# LED_ROWS.net
KiCad netlist of a schematic drawn in Altium Designer
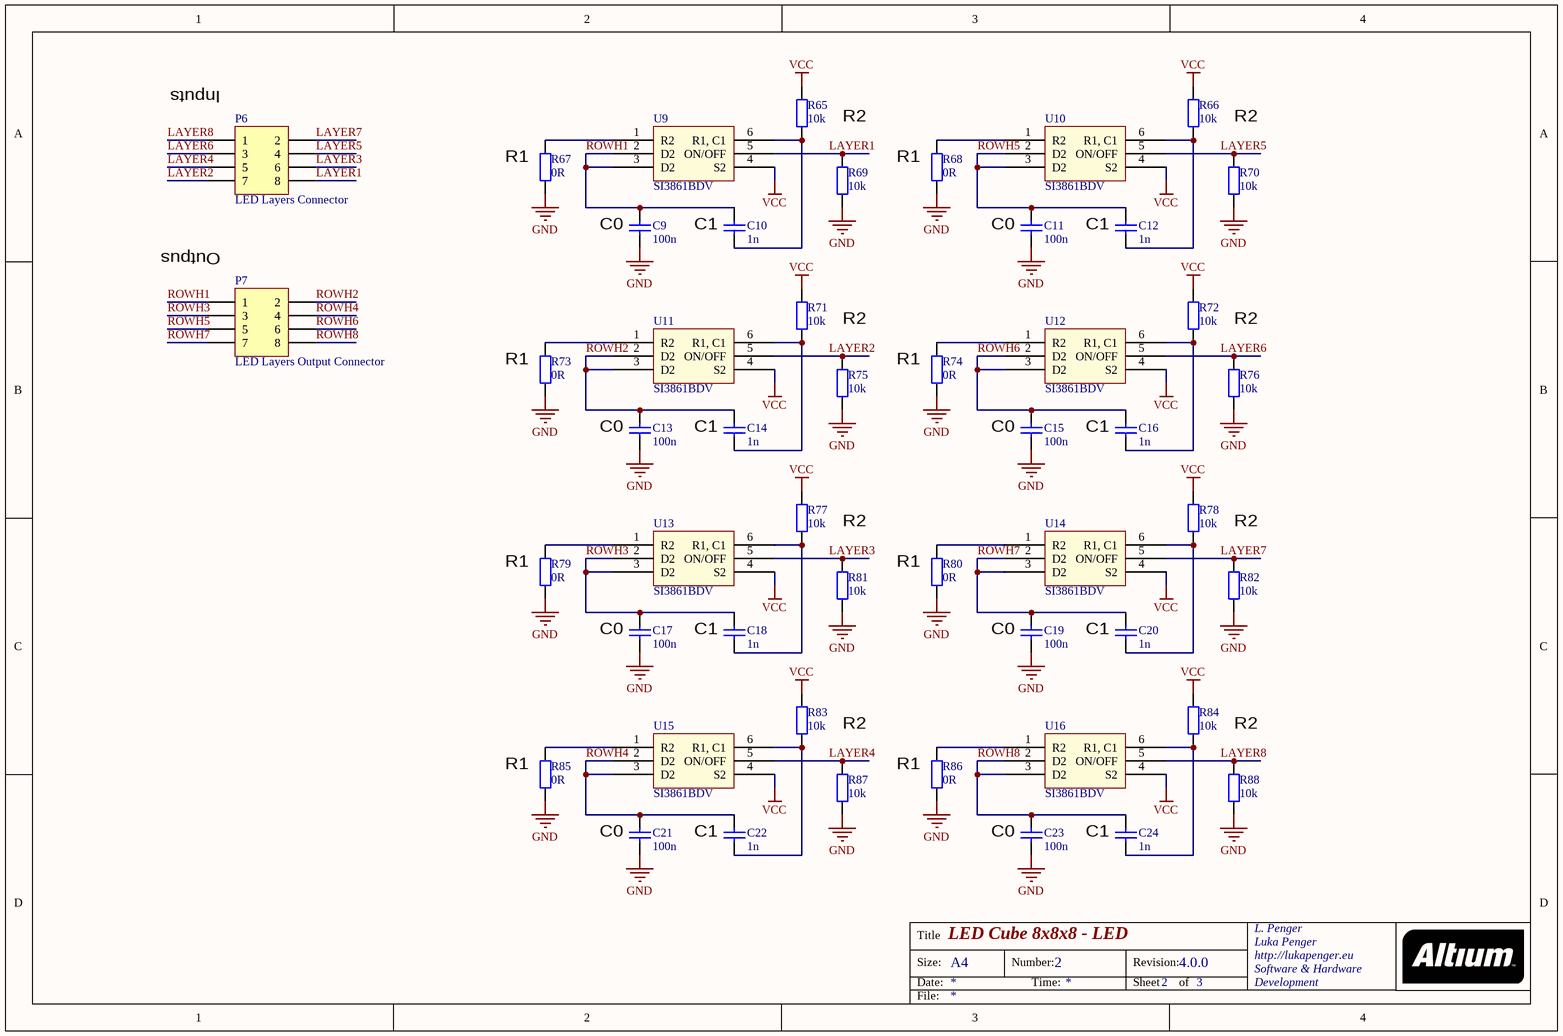
[diagram p0: LED_ROWS.SchDoc]

(export (version "E")
  (design (tool "Eeschema 10.0.6"))
  (components
    (comp (ref "C9")
      (value "100n")
      (footprint "1608[0603]")
      (description "Capacitor")
      (fields (field (name "PUBLISHER") "Altium Limited"))
      (libsource (lib "Miscellaneous Devices") (part "Cap"))
    )
    (comp (ref "C10")
      (value "1n")
      (footprint "1608[0603]")
      (description "Capacitor")
      (fields (field (name "PUBLISHER") "Altium Limited"))
      (libsource (lib "Miscellaneous Devices") (part "Cap"))
    )
    (comp (ref "C11")
      (value "100n")
      (footprint "1608[0603]")
      (description "Capacitor")
      (fields (field (name "PUBLISHER") "Altium Limited"))
      (libsource (lib "Miscellaneous Devices") (part "Cap"))
    )
    (comp (ref "C12")
      (value "1n")
      (footprint "1608[0603]")
      (description "Capacitor")
      (fields (field (name "PUBLISHER") "Altium Limited"))
      (libsource (lib "Miscellaneous Devices") (part "Cap"))
    )
    (comp (ref "C13")
      (value "100n")
      (footprint "1608[0603]")
      (description "Capacitor")
      (fields (field (name "PUBLISHER") "Altium Limited"))
      (libsource (lib "Miscellaneous Devices") (part "Cap"))
    )
    (comp (ref "C14")
      (value "1n")
      (footprint "1608[0603]")
      (description "Capacitor")
      (fields (field (name "PUBLISHER") "Altium Limited"))
      (libsource (lib "Miscellaneous Devices") (part "Cap"))
    )
    (comp (ref "C15")
      (value "100n")
      (footprint "1608[0603]")
      (description "Capacitor")
      (fields (field (name "PUBLISHER") "Altium Limited"))
      (libsource (lib "Miscellaneous Devices") (part "Cap"))
    )
    (comp (ref "C16")
      (value "1n")
      (footprint "1608[0603]")
      (description "Capacitor")
      (fields (field (name "PUBLISHER") "Altium Limited"))
      (libsource (lib "Miscellaneous Devices") (part "Cap"))
    )
    (comp (ref "C17")
      (value "100n")
      (footprint "1608[0603]")
      (description "Capacitor")
      (fields (field (name "PUBLISHER") "Altium Limited"))
      (libsource (lib "Miscellaneous Devices") (part "Cap"))
    )
    (comp (ref "C18")
      (value "1n")
      (footprint "1608[0603]")
      (description "Capacitor")
      (fields (field (name "PUBLISHER") "Altium Limited"))
      (libsource (lib "Miscellaneous Devices") (part "Cap"))
    )
    (comp (ref "C19")
      (value "100n")
      (footprint "1608[0603]")
      (description "Capacitor")
      (fields (field (name "PUBLISHER") "Altium Limited"))
      (libsource (lib "Miscellaneous Devices") (part "Cap"))
    )
    (comp (ref "C20")
      (value "1n")
      (footprint "1608[0603]")
      (description "Capacitor")
      (fields (field (name "PUBLISHER") "Altium Limited"))
      (libsource (lib "Miscellaneous Devices") (part "Cap"))
    )
    (comp (ref "C21")
      (value "100n")
      (footprint "1608[0603]")
      (description "Capacitor")
      (fields (field (name "PUBLISHER") "Altium Limited"))
      (libsource (lib "Miscellaneous Devices") (part "Cap"))
    )
    (comp (ref "C22")
      (value "1n")
      (footprint "1608[0603]")
      (description "Capacitor")
      (fields (field (name "PUBLISHER") "Altium Limited"))
      (libsource (lib "Miscellaneous Devices") (part "Cap"))
    )
    (comp (ref "C23")
      (value "100n")
      (footprint "1608[0603]")
      (description "Capacitor")
      (fields (field (name "PUBLISHER") "Altium Limited"))
      (libsource (lib "Miscellaneous Devices") (part "Cap"))
    )
    (comp (ref "C24")
      (value "1n")
      (footprint "1608[0603]")
      (description "Capacitor")
      (fields (field (name "PUBLISHER") "Altium Limited"))
      (libsource (lib "Miscellaneous Devices") (part "Cap"))
    )
    (comp (ref "P6")
      (value "LED Layers Connector")
      (footprint "IDC-2x4")
      (description "Header, 4-Pin, Dual row")
      (fields (field (name "PUBLISHER") "Altium Limited"))
      (libsource (lib "Miscellaneous Connectors") (part "Header 4X2"))
    )
    (comp (ref "P7")
      (value "LED Layers Output Connector")
      (footprint "IDC-2x4")
      (description "Header, 4-Pin, Dual row")
      (fields (field (name "PUBLISHER") "Altium Limited"))
      (libsource (lib "Miscellaneous Connectors") (part "Header 4X2"))
    )
    (comp (ref "R65")
      (value "10k")
      (footprint "1608[0603]")
      (description "Resistor")
      (fields (field (name "PUBLISHER") "Altium Limited"))
      (libsource (lib "Miscellaneous Devices") (part "Res2"))
    )
    (comp (ref "R66")
      (value "10k")
      (footprint "1608[0603]")
      (description "Resistor")
      (fields (field (name "PUBLISHER") "Altium Limited"))
      (libsource (lib "Miscellaneous Devices") (part "Res2"))
    )
    (comp (ref "R67")
      (value "0R")
      (footprint "1608[0603]")
      (description "Resistor")
      (fields (field (name "PUBLISHER") "Altium Limited"))
      (libsource (lib "") (part "Res2_1"))
    )
    (comp (ref "R68")
      (value "0R")
      (footprint "1608[0603]")
      (description "Resistor")
      (fields (field (name "PUBLISHER") "Altium Limited"))
      (libsource (lib "") (part "Res2_1"))
    )
    (comp (ref "R69")
      (value "10k")
      (footprint "1608[0603]")
      (description "Resistor")
      (fields (field (name "PUBLISHER") "Altium Limited"))
      (libsource (lib "Miscellaneous Devices") (part "Res2"))
    )
    (comp (ref "R70")
      (value "10k")
      (footprint "1608[0603]")
      (description "Resistor")
      (fields (field (name "PUBLISHER") "Altium Limited"))
      (libsource (lib "Miscellaneous Devices") (part "Res2"))
    )
    (comp (ref "R71")
      (value "10k")
      (footprint "1608[0603]")
      (description "Resistor")
      (fields (field (name "PUBLISHER") "Altium Limited"))
      (libsource (lib "Miscellaneous Devices") (part "Res2"))
    )
    (comp (ref "R72")
      (value "10k")
      (footprint "1608[0603]")
      (description "Resistor")
      (fields (field (name "PUBLISHER") "Altium Limited"))
      (libsource (lib "Miscellaneous Devices") (part "Res2"))
    )
    (comp (ref "R73")
      (value "0R")
      (footprint "1608[0603]")
      (description "Resistor")
      (fields (field (name "PUBLISHER") "Altium Limited"))
      (libsource (lib "") (part "Res2_1"))
    )
    (comp (ref "R74")
      (value "0R")
      (footprint "1608[0603]")
      (description "Resistor")
      (fields (field (name "PUBLISHER") "Altium Limited"))
      (libsource (lib "") (part "Res2_1"))
    )
    (comp (ref "R75")
      (value "10k")
      (footprint "1608[0603]")
      (description "Resistor")
      (fields (field (name "PUBLISHER") "Altium Limited"))
      (libsource (lib "Miscellaneous Devices") (part "Res2"))
    )
    (comp (ref "R76")
      (value "10k")
      (footprint "1608[0603]")
      (description "Resistor")
      (fields (field (name "PUBLISHER") "Altium Limited"))
      (libsource (lib "Miscellaneous Devices") (part "Res2"))
    )
    (comp (ref "R77")
      (value "10k")
      (footprint "1608[0603]")
      (description "Resistor")
      (fields (field (name "PUBLISHER") "Altium Limited"))
      (libsource (lib "Miscellaneous Devices") (part "Res2"))
    )
    (comp (ref "R78")
      (value "10k")
      (footprint "1608[0603]")
      (description "Resistor")
      (fields (field (name "PUBLISHER") "Altium Limited"))
      (libsource (lib "Miscellaneous Devices") (part "Res2"))
    )
    (comp (ref "R79")
      (value "0R")
      (footprint "1608[0603]")
      (description "Resistor")
      (fields (field (name "PUBLISHER") "Altium Limited"))
      (libsource (lib "") (part "Res2_1"))
    )
    (comp (ref "R80")
      (value "0R")
      (footprint "1608[0603]")
      (description "Resistor")
      (fields (field (name "PUBLISHER") "Altium Limited"))
      (libsource (lib "") (part "Res2_1"))
    )
    (comp (ref "R81")
      (value "10k")
      (footprint "1608[0603]")
      (description "Resistor")
      (fields (field (name "PUBLISHER") "Altium Limited"))
      (libsource (lib "Miscellaneous Devices") (part "Res2"))
    )
    (comp (ref "R82")
      (value "10k")
      (footprint "1608[0603]")
      (description "Resistor")
      (fields (field (name "PUBLISHER") "Altium Limited"))
      (libsource (lib "Miscellaneous Devices") (part "Res2"))
    )
    (comp (ref "R83")
      (value "10k")
      (footprint "1608[0603]")
      (description "Resistor")
      (fields (field (name "PUBLISHER") "Altium Limited"))
      (libsource (lib "Miscellaneous Devices") (part "Res2"))
    )
    (comp (ref "R84")
      (value "10k")
      (footprint "1608[0603]")
      (description "Resistor")
      (fields (field (name "PUBLISHER") "Altium Limited"))
      (libsource (lib "Miscellaneous Devices") (part "Res2"))
    )
    (comp (ref "R85")
      (value "0R")
      (footprint "1608[0603]")
      (description "Resistor")
      (fields (field (name "PUBLISHER") "Altium Limited"))
      (libsource (lib "") (part "Res2_1"))
    )
    (comp (ref "R86")
      (value "0R")
      (footprint "1608[0603]")
      (description "Resistor")
      (fields (field (name "PUBLISHER") "Altium Limited"))
      (libsource (lib "") (part "Res2_1"))
    )
    (comp (ref "R87")
      (value "10k")
      (footprint "1608[0603]")
      (description "Resistor")
      (fields (field (name "PUBLISHER") "Altium Limited"))
      (libsource (lib "Miscellaneous Devices") (part "Res2"))
    )
    (comp (ref "R88")
      (value "10k")
      (footprint "1608[0603]")
      (description "Resistor")
      (fields (field (name "PUBLISHER") "Altium Limited"))
      (libsource (lib "Miscellaneous Devices") (part "Res2"))
    )
    (comp (ref "U9")
      (value "SI3861BDV")
      (footprint "TSOP 6")
      (description "4.5 - 20V 2.3A Load Switch")
      (libsource (lib "LukaLIBRARY") (part "SI3861BDV"))
    )
    (comp (ref "U10")
      (value "SI3861BDV")
      (footprint "TSOP 6")
      (description "4.5 - 20V 2.3A Load Switch")
      (libsource (lib "LukaLIBRARY") (part "SI3861BDV"))
    )
    (comp (ref "U11")
      (value "SI3861BDV")
      (footprint "TSOP 6")
      (description "4.5 - 20V 2.3A Load Switch")
      (libsource (lib "LukaLIBRARY") (part "SI3861BDV"))
    )
    (comp (ref "U12")
      (value "SI3861BDV")
      (footprint "TSOP 6")
      (description "4.5 - 20V 2.3A Load Switch")
      (libsource (lib "LukaLIBRARY") (part "SI3861BDV"))
    )
    (comp (ref "U13")
      (value "SI3861BDV")
      (footprint "TSOP 6")
      (description "4.5 - 20V 2.3A Load Switch")
      (libsource (lib "LukaLIBRARY") (part "SI3861BDV"))
    )
    (comp (ref "U14")
      (value "SI3861BDV")
      (footprint "TSOP 6")
      (description "4.5 - 20V 2.3A Load Switch")
      (libsource (lib "LukaLIBRARY") (part "SI3861BDV"))
    )
    (comp (ref "U15")
      (value "SI3861BDV")
      (footprint "TSOP 6")
      (description "4.5 - 20V 2.3A Load Switch")
      (libsource (lib "LukaLIBRARY") (part "SI3861BDV"))
    )
    (comp (ref "U16")
      (value "SI3861BDV")
      (footprint "TSOP 6")
      (description "4.5 - 20V 2.3A Load Switch")
      (libsource (lib "LukaLIBRARY") (part "SI3861BDV"))
    )
  )
  (nets
    (net (code "1") (name "/LAYER1") (class "Default")
      (node (ref "P6") (pin "8") (pinfunction "8_8") (pintype "passive"))
      (node (ref "R69") (pin "2") (pinfunction "2_2") (pintype "passive"))
      (node (ref "U9") (pin "5") (pinfunction "ON/OFF_5") (pintype "passive"))
    )
    (net (code "2") (name "/LAYER2") (class "Default")
      (node (ref "P6") (pin "7") (pinfunction "7_7") (pintype "passive"))
      (node (ref "R75") (pin "2") (pinfunction "2_2") (pintype "passive"))
      (node (ref "U11") (pin "5") (pinfunction "ON/OFF_5") (pintype "passive"))
    )
    (net (code "3") (name "/LAYER3") (class "Default")
      (node (ref "P6") (pin "6") (pinfunction "6_6") (pintype "passive"))
      (node (ref "R81") (pin "2") (pinfunction "2_2") (pintype "passive"))
      (node (ref "U13") (pin "5") (pinfunction "ON/OFF_5") (pintype "passive"))
    )
    (net (code "4") (name "/LAYER4") (class "Default")
      (node (ref "P6") (pin "5") (pinfunction "5_5") (pintype "passive"))
      (node (ref "R87") (pin "2") (pinfunction "2_2") (pintype "passive"))
      (node (ref "U15") (pin "5") (pinfunction "ON/OFF_5") (pintype "passive"))
    )
    (net (code "5") (name "/LAYER5") (class "Default")
      (node (ref "P6") (pin "4") (pinfunction "4_4") (pintype "passive"))
      (node (ref "R70") (pin "2") (pinfunction "2_2") (pintype "passive"))
      (node (ref "U10") (pin "5") (pinfunction "ON/OFF_5") (pintype "passive"))
    )
    (net (code "6") (name "/LAYER6") (class "Default")
      (node (ref "P6") (pin "3") (pinfunction "3_3") (pintype "passive"))
      (node (ref "R76") (pin "2") (pinfunction "2_2") (pintype "passive"))
      (node (ref "U12") (pin "5") (pinfunction "ON/OFF_5") (pintype "passive"))
    )
    (net (code "7") (name "/LAYER7") (class "Default")
      (node (ref "P6") (pin "2") (pinfunction "2_2") (pintype "passive"))
      (node (ref "R82") (pin "2") (pinfunction "2_2") (pintype "passive"))
      (node (ref "U14") (pin "5") (pinfunction "ON/OFF_5") (pintype "passive"))
    )
    (net (code "8") (name "/LAYER8") (class "Default")
      (node (ref "P6") (pin "1") (pinfunction "1_1") (pintype "passive"))
      (node (ref "R88") (pin "2") (pinfunction "2_2") (pintype "passive"))
      (node (ref "U16") (pin "5") (pinfunction "ON/OFF_5") (pintype "passive"))
    )
    (net (code "9") (name "/ROWH1") (class "Default")
      (node (ref "C10") (pin "1") (pinfunction "1_1") (pintype "passive"))
      (node (ref "C9") (pin "1") (pinfunction "1_1") (pintype "passive"))
      (node (ref "P7") (pin "1") (pinfunction "1_1") (pintype "passive"))
      (node (ref "U9") (pin "2") (pinfunction "D2_2") (pintype "passive"))
      (node (ref "U9") (pin "3") (pinfunction "D2_3") (pintype "passive"))
    )
    (net (code "10") (name "/ROWH2") (class "Default")
      (node (ref "C13") (pin "1") (pinfunction "1_1") (pintype "passive"))
      (node (ref "C14") (pin "1") (pinfunction "1_1") (pintype "passive"))
      (node (ref "P7") (pin "2") (pinfunction "2_2") (pintype "passive"))
      (node (ref "U11") (pin "2") (pinfunction "D2_2") (pintype "passive"))
      (node (ref "U11") (pin "3") (pinfunction "D2_3") (pintype "passive"))
    )
    (net (code "11") (name "/ROWH3") (class "Default")
      (node (ref "C17") (pin "1") (pinfunction "1_1") (pintype "passive"))
      (node (ref "C18") (pin "1") (pinfunction "1_1") (pintype "passive"))
      (node (ref "P7") (pin "3") (pinfunction "3_3") (pintype "passive"))
      (node (ref "U13") (pin "2") (pinfunction "D2_2") (pintype "passive"))
      (node (ref "U13") (pin "3") (pinfunction "D2_3") (pintype "passive"))
    )
    (net (code "12") (name "/ROWH4") (class "Default")
      (node (ref "C21") (pin "1") (pinfunction "1_1") (pintype "passive"))
      (node (ref "C22") (pin "1") (pinfunction "1_1") (pintype "passive"))
      (node (ref "P7") (pin "4") (pinfunction "4_4") (pintype "passive"))
      (node (ref "U15") (pin "2") (pinfunction "D2_2") (pintype "passive"))
      (node (ref "U15") (pin "3") (pinfunction "D2_3") (pintype "passive"))
    )
    (net (code "13") (name "/ROWH5") (class "Default")
      (node (ref "C11") (pin "1") (pinfunction "1_1") (pintype "passive"))
      (node (ref "C12") (pin "1") (pinfunction "1_1") (pintype "passive"))
      (node (ref "P7") (pin "5") (pinfunction "5_5") (pintype "passive"))
      (node (ref "U10") (pin "2") (pinfunction "D2_2") (pintype "passive"))
      (node (ref "U10") (pin "3") (pinfunction "D2_3") (pintype "passive"))
    )
    (net (code "14") (name "/ROWH6") (class "Default")
      (node (ref "C15") (pin "1") (pinfunction "1_1") (pintype "passive"))
      (node (ref "C16") (pin "1") (pinfunction "1_1") (pintype "passive"))
      (node (ref "P7") (pin "6") (pinfunction "6_6") (pintype "passive"))
      (node (ref "U12") (pin "2") (pinfunction "D2_2") (pintype "passive"))
      (node (ref "U12") (pin "3") (pinfunction "D2_3") (pintype "passive"))
    )
    (net (code "15") (name "/ROWH7") (class "Default")
      (node (ref "C19") (pin "1") (pinfunction "1_1") (pintype "passive"))
      (node (ref "C20") (pin "1") (pinfunction "1_1") (pintype "passive"))
      (node (ref "P7") (pin "7") (pinfunction "7_7") (pintype "passive"))
      (node (ref "U14") (pin "2") (pinfunction "D2_2") (pintype "passive"))
      (node (ref "U14") (pin "3") (pinfunction "D2_3") (pintype "passive"))
    )
    (net (code "16") (name "/ROWH8") (class "Default")
      (node (ref "C23") (pin "1") (pinfunction "1_1") (pintype "passive"))
      (node (ref "C24") (pin "1") (pinfunction "1_1") (pintype "passive"))
      (node (ref "P7") (pin "8") (pinfunction "8_8") (pintype "passive"))
      (node (ref "U16") (pin "2") (pinfunction "D2_2") (pintype "passive"))
      (node (ref "U16") (pin "3") (pinfunction "D2_3") (pintype "passive"))
    )
    (net (code "17") (name "GND") (class "Default")
      (node (ref "C11") (pin "2") (pinfunction "2_2") (pintype "passive"))
      (node (ref "C13") (pin "2") (pinfunction "2_2") (pintype "passive"))
      (node (ref "C15") (pin "2") (pinfunction "2_2") (pintype "passive"))
      (node (ref "C17") (pin "2") (pinfunction "2_2") (pintype "passive"))
      (node (ref "C19") (pin "2") (pinfunction "2_2") (pintype "passive"))
      (node (ref "C21") (pin "2") (pinfunction "2_2") (pintype "passive"))
      (node (ref "C23") (pin "2") (pinfunction "2_2") (pintype "passive"))
      (node (ref "C9") (pin "2") (pinfunction "2_2") (pintype "passive"))
      (node (ref "R67") (pin "2") (pinfunction "2_2") (pintype "passive"))
      (node (ref "R68") (pin "2") (pinfunction "2_2") (pintype "passive"))
      (node (ref "R69") (pin "1") (pinfunction "1_1") (pintype "passive"))
      (node (ref "R70") (pin "1") (pinfunction "1_1") (pintype "passive"))
      (node (ref "R73") (pin "2") (pinfunction "2_2") (pintype "passive"))
      (node (ref "R74") (pin "2") (pinfunction "2_2") (pintype "passive"))
      (node (ref "R75") (pin "1") (pinfunction "1_1") (pintype "passive"))
      (node (ref "R76") (pin "1") (pinfunction "1_1") (pintype "passive"))
      (node (ref "R79") (pin "2") (pinfunction "2_2") (pintype "passive"))
      (node (ref "R80") (pin "2") (pinfunction "2_2") (pintype "passive"))
      (node (ref "R81") (pin "1") (pinfunction "1_1") (pintype "passive"))
      (node (ref "R82") (pin "1") (pinfunction "1_1") (pintype "passive"))
      (node (ref "R85") (pin "2") (pinfunction "2_2") (pintype "passive"))
      (node (ref "R86") (pin "2") (pinfunction "2_2") (pintype "passive"))
      (node (ref "R87") (pin "1") (pinfunction "1_1") (pintype "passive"))
      (node (ref "R88") (pin "1") (pinfunction "1_1") (pintype "passive"))
    )
    (net (code "18") (name "Net-(U9-R1,_C1)") (class "Default")
      (node (ref "C10") (pin "2") (pinfunction "2_2") (pintype "passive"))
      (node (ref "R65") (pin "1") (pinfunction "1_1") (pintype "passive"))
      (node (ref "U9") (pin "6") (pinfunction "R1,_C1_6") (pintype "passive"))
    )
    (net (code "19") (name "Net-(U9-R2)") (class "Default")
      (node (ref "R67") (pin "1") (pinfunction "1_1") (pintype "passive"))
      (node (ref "U9") (pin "1") (pinfunction "R2_1") (pintype "passive"))
    )
    (net (code "20") (name "Net-(U10-R1,_C1)") (class "Default")
      (node (ref "C12") (pin "2") (pinfunction "2_2") (pintype "passive"))
      (node (ref "R66") (pin "1") (pinfunction "1_1") (pintype "passive"))
      (node (ref "U10") (pin "6") (pinfunction "R1,_C1_6") (pintype "passive"))
    )
    (net (code "21") (name "Net-(U10-R2)") (class "Default")
      (node (ref "R68") (pin "1") (pinfunction "1_1") (pintype "passive"))
      (node (ref "U10") (pin "1") (pinfunction "R2_1") (pintype "passive"))
    )
    (net (code "22") (name "Net-(U11-R1,_C1)") (class "Default")
      (node (ref "C14") (pin "2") (pinfunction "2_2") (pintype "passive"))
      (node (ref "R71") (pin "1") (pinfunction "1_1") (pintype "passive"))
      (node (ref "U11") (pin "6") (pinfunction "R1,_C1_6") (pintype "passive"))
    )
    (net (code "23") (name "Net-(U11-R2)") (class "Default")
      (node (ref "R73") (pin "1") (pinfunction "1_1") (pintype "passive"))
      (node (ref "U11") (pin "1") (pinfunction "R2_1") (pintype "passive"))
    )
    (net (code "24") (name "Net-(U12-R1,_C1)") (class "Default")
      (node (ref "C16") (pin "2") (pinfunction "2_2") (pintype "passive"))
      (node (ref "R72") (pin "1") (pinfunction "1_1") (pintype "passive"))
      (node (ref "U12") (pin "6") (pinfunction "R1,_C1_6") (pintype "passive"))
    )
    (net (code "25") (name "Net-(U12-R2)") (class "Default")
      (node (ref "R74") (pin "1") (pinfunction "1_1") (pintype "passive"))
      (node (ref "U12") (pin "1") (pinfunction "R2_1") (pintype "passive"))
    )
    (net (code "26") (name "Net-(U13-R1,_C1)") (class "Default")
      (node (ref "C18") (pin "2") (pinfunction "2_2") (pintype "passive"))
      (node (ref "R77") (pin "1") (pinfunction "1_1") (pintype "passive"))
      (node (ref "U13") (pin "6") (pinfunction "R1,_C1_6") (pintype "passive"))
    )
    (net (code "27") (name "Net-(U13-R2)") (class "Default")
      (node (ref "R79") (pin "1") (pinfunction "1_1") (pintype "passive"))
      (node (ref "U13") (pin "1") (pinfunction "R2_1") (pintype "passive"))
    )
    (net (code "28") (name "Net-(U14-R1,_C1)") (class "Default")
      (node (ref "C20") (pin "2") (pinfunction "2_2") (pintype "passive"))
      (node (ref "R78") (pin "1") (pinfunction "1_1") (pintype "passive"))
      (node (ref "U14") (pin "6") (pinfunction "R1,_C1_6") (pintype "passive"))
    )
    (net (code "29") (name "Net-(U14-R2)") (class "Default")
      (node (ref "R80") (pin "1") (pinfunction "1_1") (pintype "passive"))
      (node (ref "U14") (pin "1") (pinfunction "R2_1") (pintype "passive"))
    )
    (net (code "30") (name "Net-(U15-R1,_C1)") (class "Default")
      (node (ref "C22") (pin "2") (pinfunction "2_2") (pintype "passive"))
      (node (ref "R83") (pin "1") (pinfunction "1_1") (pintype "passive"))
      (node (ref "U15") (pin "6") (pinfunction "R1,_C1_6") (pintype "passive"))
    )
    (net (code "31") (name "Net-(U15-R2)") (class "Default")
      (node (ref "R85") (pin "1") (pinfunction "1_1") (pintype "passive"))
      (node (ref "U15") (pin "1") (pinfunction "R2_1") (pintype "passive"))
    )
    (net (code "32") (name "Net-(U16-R1,_C1)") (class "Default")
      (node (ref "C24") (pin "2") (pinfunction "2_2") (pintype "passive"))
      (node (ref "R84") (pin "1") (pinfunction "1_1") (pintype "passive"))
      (node (ref "U16") (pin "6") (pinfunction "R1,_C1_6") (pintype "passive"))
    )
    (net (code "33") (name "Net-(U16-R2)") (class "Default")
      (node (ref "R86") (pin "1") (pinfunction "1_1") (pintype "passive"))
      (node (ref "U16") (pin "1") (pinfunction "R2_1") (pintype "passive"))
    )
    (net (code "34") (name "VCC") (class "Default")
      (node (ref "R65") (pin "2") (pinfunction "2_2") (pintype "passive"))
      (node (ref "R66") (pin "2") (pinfunction "2_2") (pintype "passive"))
      (node (ref "R71") (pin "2") (pinfunction "2_2") (pintype "passive"))
      (node (ref "R72") (pin "2") (pinfunction "2_2") (pintype "passive"))
      (node (ref "R77") (pin "2") (pinfunction "2_2") (pintype "passive"))
      (node (ref "R78") (pin "2") (pinfunction "2_2") (pintype "passive"))
      (node (ref "R83") (pin "2") (pinfunction "2_2") (pintype "passive"))
      (node (ref "R84") (pin "2") (pinfunction "2_2") (pintype "passive"))
      (node (ref "U10") (pin "4") (pinfunction "S2_4") (pintype "passive"))
      (node (ref "U11") (pin "4") (pinfunction "S2_4") (pintype "passive"))
      (node (ref "U12") (pin "4") (pinfunction "S2_4") (pintype "passive"))
      (node (ref "U13") (pin "4") (pinfunction "S2_4") (pintype "passive"))
      (node (ref "U14") (pin "4") (pinfunction "S2_4") (pintype "passive"))
      (node (ref "U15") (pin "4") (pinfunction "S2_4") (pintype "passive"))
      (node (ref "U16") (pin "4") (pinfunction "S2_4") (pintype "passive"))
      (node (ref "U9") (pin "4") (pinfunction "S2_4") (pintype "passive"))
    )
  )
)
